# ruralhack-board-r2.net
KiCad netlist of a schematic drawn in EAGLE
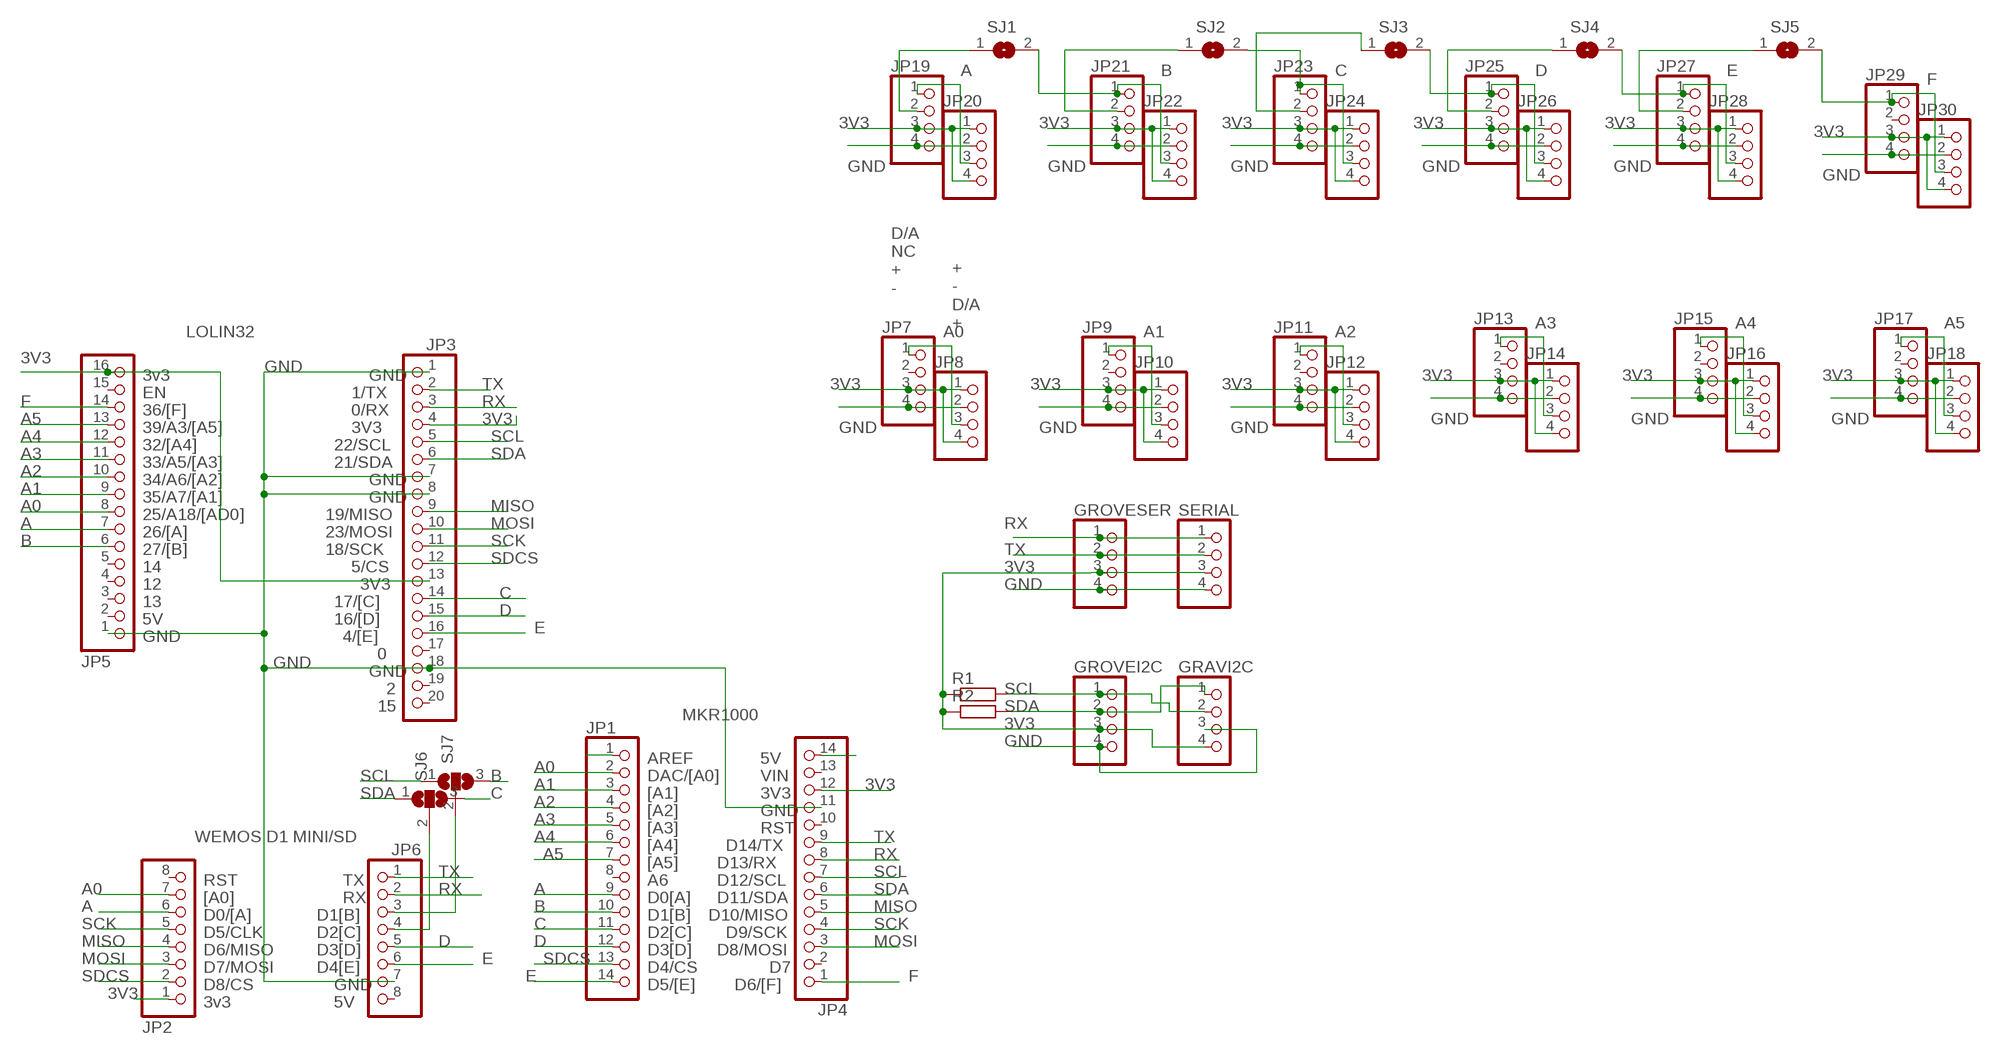
[diagram p0: schematic, sheet 1]

(export (version "E")
  (design (tool "Eeschema 10.0.6"))
  (components
    (comp (ref "GRAVI2C")
      (value "PINHD-1X4")
      (footprint "eagle-import:1X04")
      (libsource (lib "eagle-import") (part "PINHD-1X4"))
    )
    (comp (ref "GROVEI2C")
      (value "PINHD-1X4")
      (footprint "eagle-import:1X04")
      (libsource (lib "eagle-import") (part "PINHD-1X4"))
    )
    (comp (ref "GROVESER")
      (value "PINHD-1X4")
      (footprint "eagle-import:1X04")
      (libsource (lib "eagle-import") (part "PINHD-1X4"))
    )
    (comp (ref "JP1")
      (value "PINHD-1X14")
      (footprint "eagle-import:1X14")
      (libsource (lib "eagle-import") (part "PINHD-1X14"))
    )
    (comp (ref "JP2")
      (value "PINHD-1X8")
      (footprint "eagle-import:1X08")
      (libsource (lib "eagle-import") (part "PINHD-1X8"))
    )
    (comp (ref "JP3")
      (value "PINHD-1X20")
      (footprint "eagle-import:1X20")
      (libsource (lib "eagle-import") (part "PINHD-1X20"))
    )
    (comp (ref "JP4")
      (value "PINHD-1X14")
      (footprint "eagle-import:1X14")
      (libsource (lib "eagle-import") (part "PINHD-1X14"))
    )
    (comp (ref "JP5")
      (value "PINHD-1X16")
      (footprint "eagle-import:1X16")
      (libsource (lib "eagle-import") (part "PINHD-1X16"))
    )
    (comp (ref "JP6")
      (value "PINHD-1X8")
      (footprint "eagle-import:1X08")
      (libsource (lib "eagle-import") (part "PINHD-1X8"))
    )
    (comp (ref "JP7")
      (value "PINHD-1X4")
      (footprint "eagle-import:1X04")
      (libsource (lib "eagle-import") (part "PINHD-1X4"))
    )
    (comp (ref "JP8")
      (value "PINHD-1X4")
      (footprint "eagle-import:1X04")
      (libsource (lib "eagle-import") (part "PINHD-1X4"))
    )
    (comp (ref "JP9")
      (value "PINHD-1X4")
      (footprint "eagle-import:1X04")
      (libsource (lib "eagle-import") (part "PINHD-1X4"))
    )
    (comp (ref "JP10")
      (value "PINHD-1X4")
      (footprint "eagle-import:1X04")
      (libsource (lib "eagle-import") (part "PINHD-1X4"))
    )
    (comp (ref "JP11")
      (value "PINHD-1X4")
      (footprint "eagle-import:1X04")
      (libsource (lib "eagle-import") (part "PINHD-1X4"))
    )
    (comp (ref "JP12")
      (value "PINHD-1X4")
      (footprint "eagle-import:1X04")
      (libsource (lib "eagle-import") (part "PINHD-1X4"))
    )
    (comp (ref "JP13")
      (value "PINHD-1X4")
      (footprint "eagle-import:1X04")
      (libsource (lib "eagle-import") (part "PINHD-1X4"))
    )
    (comp (ref "JP14")
      (value "PINHD-1X4")
      (footprint "eagle-import:1X04")
      (libsource (lib "eagle-import") (part "PINHD-1X4"))
    )
    (comp (ref "JP15")
      (value "PINHD-1X4")
      (footprint "eagle-import:1X04")
      (libsource (lib "eagle-import") (part "PINHD-1X4"))
    )
    (comp (ref "JP16")
      (value "PINHD-1X4")
      (footprint "eagle-import:1X04")
      (libsource (lib "eagle-import") (part "PINHD-1X4"))
    )
    (comp (ref "JP17")
      (value "PINHD-1X4")
      (footprint "eagle-import:1X04")
      (libsource (lib "eagle-import") (part "PINHD-1X4"))
    )
    (comp (ref "JP18")
      (value "PINHD-1X4")
      (footprint "eagle-import:1X04")
      (libsource (lib "eagle-import") (part "PINHD-1X4"))
    )
    (comp (ref "JP19")
      (value "PINHD-1X4")
      (footprint "eagle-import:1X04")
      (libsource (lib "eagle-import") (part "PINHD-1X4"))
    )
    (comp (ref "JP20")
      (value "PINHD-1X4")
      (footprint "eagle-import:1X04")
      (libsource (lib "eagle-import") (part "PINHD-1X4"))
    )
    (comp (ref "JP21")
      (value "PINHD-1X4")
      (footprint "eagle-import:1X04")
      (libsource (lib "eagle-import") (part "PINHD-1X4"))
    )
    (comp (ref "JP22")
      (value "PINHD-1X4")
      (footprint "eagle-import:1X04")
      (libsource (lib "eagle-import") (part "PINHD-1X4"))
    )
    (comp (ref "JP23")
      (value "PINHD-1X4")
      (footprint "eagle-import:1X04")
      (libsource (lib "eagle-import") (part "PINHD-1X4"))
    )
    (comp (ref "JP24")
      (value "PINHD-1X4")
      (footprint "eagle-import:1X04")
      (libsource (lib "eagle-import") (part "PINHD-1X4"))
    )
    (comp (ref "JP25")
      (value "PINHD-1X4")
      (footprint "eagle-import:1X04")
      (libsource (lib "eagle-import") (part "PINHD-1X4"))
    )
    (comp (ref "JP26")
      (value "PINHD-1X4")
      (footprint "eagle-import:1X04")
      (libsource (lib "eagle-import") (part "PINHD-1X4"))
    )
    (comp (ref "JP27")
      (value "PINHD-1X4")
      (footprint "eagle-import:1X04")
      (libsource (lib "eagle-import") (part "PINHD-1X4"))
    )
    (comp (ref "JP28")
      (value "PINHD-1X4")
      (footprint "eagle-import:1X04")
      (libsource (lib "eagle-import") (part "PINHD-1X4"))
    )
    (comp (ref "JP29")
      (value "PINHD-1X4")
      (footprint "eagle-import:1X04")
      (libsource (lib "eagle-import") (part "PINHD-1X4"))
    )
    (comp (ref "JP30")
      (value "PINHD-1X4")
      (footprint "eagle-import:1X04")
      (libsource (lib "eagle-import") (part "PINHD-1X4"))
    )
    (comp (ref "R1")
      (value "R-EU_0204/7")
      (footprint "eagle-import:0204_7")
      (libsource (lib "eagle-import") (part "R-EU_0204/7"))
    )
    (comp (ref "R2")
      (value "R-EU_0204/7")
      (footprint "eagle-import:0204_7")
      (libsource (lib "eagle-import") (part "R-EU_0204/7"))
    )
    (comp (ref "SERIAL")
      (value "PINHD-1X4")
      (footprint "eagle-import:1X04")
      (libsource (lib "eagle-import") (part "PINHD-1X4"))
    )
    (comp (ref "SJ1")
      (value "SJW")
      (footprint "eagle-import:SJW")
      (libsource (lib "eagle-import") (part "SJW"))
    )
    (comp (ref "SJ2")
      (value "SJW")
      (footprint "eagle-import:SJW")
      (libsource (lib "eagle-import") (part "SJW"))
    )
    (comp (ref "SJ3")
      (value "SJW")
      (footprint "eagle-import:SJW")
      (libsource (lib "eagle-import") (part "SJW"))
    )
    (comp (ref "SJ4")
      (value "SJW")
      (footprint "eagle-import:SJW")
      (libsource (lib "eagle-import") (part "SJW"))
    )
    (comp (ref "SJ5")
      (value "SJW")
      (footprint "eagle-import:SJW")
      (libsource (lib "eagle-import") (part "SJW"))
    )
    (comp (ref "SJ6")
      (value "SJ2WW")
      (footprint "eagle-import:SJ_2W")
      (libsource (lib "eagle-import") (part "SJ2WW"))
    )
    (comp (ref "SJ7")
      (value "SJ2WW")
      (footprint "eagle-import:SJ_2W")
      (libsource (lib "eagle-import") (part "SJ2WW"))
    )
  )
  (nets
    (net (code "1") (name "/3V3") (class "Default")
      (node (ref "GRAVI2C") (pin "4") (pinfunction "4_4") (pintype "passive"))
      (node (ref "GROVEI2C") (pin "3") (pinfunction "3_3") (pintype "passive"))
      (node (ref "GROVESER") (pin "3") (pinfunction "3_3") (pintype "passive"))
      (node (ref "JP10") (pin "1") (pinfunction "1_1") (pintype "passive"))
      (node (ref "JP10") (pin "4") (pinfunction "4_4") (pintype "passive"))
      (node (ref "JP11") (pin "3") (pinfunction "3_3") (pintype "passive"))
      (node (ref "JP12") (pin "1") (pinfunction "1_1") (pintype "passive"))
      (node (ref "JP12") (pin "4") (pinfunction "4_4") (pintype "passive"))
      (node (ref "JP13") (pin "3") (pinfunction "3_3") (pintype "passive"))
      (node (ref "JP14") (pin "1") (pinfunction "1_1") (pintype "passive"))
      (node (ref "JP14") (pin "4") (pinfunction "4_4") (pintype "passive"))
      (node (ref "JP15") (pin "3") (pinfunction "3_3") (pintype "passive"))
      (node (ref "JP16") (pin "1") (pinfunction "1_1") (pintype "passive"))
      (node (ref "JP16") (pin "4") (pinfunction "4_4") (pintype "passive"))
      (node (ref "JP17") (pin "3") (pinfunction "3_3") (pintype "passive"))
      (node (ref "JP18") (pin "1") (pinfunction "1_1") (pintype "passive"))
      (node (ref "JP18") (pin "4") (pinfunction "4_4") (pintype "passive"))
      (node (ref "JP19") (pin "3") (pinfunction "3_3") (pintype "passive"))
      (node (ref "JP2") (pin "1") (pinfunction "1_1") (pintype "passive"))
      (node (ref "JP20") (pin "1") (pinfunction "1_1") (pintype "passive"))
      (node (ref "JP20") (pin "4") (pinfunction "4_4") (pintype "passive"))
      (node (ref "JP21") (pin "3") (pinfunction "3_3") (pintype "passive"))
      (node (ref "JP22") (pin "1") (pinfunction "1_1") (pintype "passive"))
      (node (ref "JP22") (pin "4") (pinfunction "4_4") (pintype "passive"))
      (node (ref "JP23") (pin "3") (pinfunction "3_3") (pintype "passive"))
      (node (ref "JP24") (pin "1") (pinfunction "1_1") (pintype "passive"))
      (node (ref "JP24") (pin "4") (pinfunction "4_4") (pintype "passive"))
      (node (ref "JP25") (pin "3") (pinfunction "3_3") (pintype "passive"))
      (node (ref "JP26") (pin "1") (pinfunction "1_1") (pintype "passive"))
      (node (ref "JP26") (pin "4") (pinfunction "4_4") (pintype "passive"))
      (node (ref "JP27") (pin "3") (pinfunction "3_3") (pintype "passive"))
      (node (ref "JP28") (pin "1") (pinfunction "1_1") (pintype "passive"))
      (node (ref "JP28") (pin "4") (pinfunction "4_4") (pintype "passive"))
      (node (ref "JP29") (pin "3") (pinfunction "3_3") (pintype "passive"))
      (node (ref "JP3") (pin "13") (pinfunction "13_13") (pintype "passive"))
      (node (ref "JP3") (pin "4") (pinfunction "4_4") (pintype "passive"))
      (node (ref "JP30") (pin "1") (pinfunction "1_1") (pintype "passive"))
      (node (ref "JP30") (pin "4") (pinfunction "4_4") (pintype "passive"))
      (node (ref "JP4") (pin "12") (pinfunction "12_12") (pintype "passive"))
      (node (ref "JP5") (pin "16") (pinfunction "16_16") (pintype "passive"))
      (node (ref "JP7") (pin "3") (pinfunction "3_3") (pintype "passive"))
      (node (ref "JP8") (pin "1") (pinfunction "1_1") (pintype "passive"))
      (node (ref "JP8") (pin "4") (pinfunction "4_4") (pintype "passive"))
      (node (ref "JP9") (pin "3") (pinfunction "3_3") (pintype "passive"))
      (node (ref "R1") (pin "1") (pinfunction "1_1") (pintype "passive"))
      (node (ref "R2") (pin "1") (pinfunction "1_1") (pintype "passive"))
      (node (ref "SERIAL") (pin "3") (pinfunction "3_3") (pintype "passive"))
    )
    (net (code "2") (name "/A") (class "Default")
      (node (ref "JP1") (pin "9") (pinfunction "9_9") (pintype "passive"))
      (node (ref "JP19") (pin "1") (pinfunction "1_1") (pintype "passive"))
      (node (ref "JP2") (pin "6") (pinfunction "6_6") (pintype "passive"))
      (node (ref "JP20") (pin "3") (pinfunction "3_3") (pintype "passive"))
      (node (ref "JP5") (pin "7") (pinfunction "7_7") (pintype "passive"))
    )
    (net (code "3") (name "/A0") (class "Default")
      (node (ref "JP1") (pin "2") (pinfunction "2_2") (pintype "passive"))
      (node (ref "JP2") (pin "7") (pinfunction "7_7") (pintype "passive"))
      (node (ref "JP5") (pin "8") (pinfunction "8_8") (pintype "passive"))
      (node (ref "JP7") (pin "1") (pinfunction "1_1") (pintype "passive"))
      (node (ref "JP8") (pin "3") (pinfunction "3_3") (pintype "passive"))
    )
    (net (code "4") (name "/A1") (class "Default")
      (node (ref "JP1") (pin "3") (pinfunction "3_3") (pintype "passive"))
      (node (ref "JP10") (pin "3") (pinfunction "3_3") (pintype "passive"))
      (node (ref "JP5") (pin "9") (pinfunction "9_9") (pintype "passive"))
      (node (ref "JP9") (pin "1") (pinfunction "1_1") (pintype "passive"))
    )
    (net (code "5") (name "/A2") (class "Default")
      (node (ref "JP1") (pin "4") (pinfunction "4_4") (pintype "passive"))
      (node (ref "JP11") (pin "1") (pinfunction "1_1") (pintype "passive"))
      (node (ref "JP12") (pin "3") (pinfunction "3_3") (pintype "passive"))
      (node (ref "JP5") (pin "10") (pinfunction "10_10") (pintype "passive"))
    )
    (net (code "6") (name "/A3") (class "Default")
      (node (ref "JP1") (pin "5") (pinfunction "5_5") (pintype "passive"))
      (node (ref "JP13") (pin "1") (pinfunction "1_1") (pintype "passive"))
      (node (ref "JP14") (pin "3") (pinfunction "3_3") (pintype "passive"))
      (node (ref "JP5") (pin "11") (pinfunction "11_11") (pintype "passive"))
    )
    (net (code "7") (name "/A4") (class "Default")
      (node (ref "JP1") (pin "6") (pinfunction "6_6") (pintype "passive"))
      (node (ref "JP15") (pin "1") (pinfunction "1_1") (pintype "passive"))
      (node (ref "JP16") (pin "3") (pinfunction "3_3") (pintype "passive"))
      (node (ref "JP5") (pin "12") (pinfunction "12_12") (pintype "passive"))
    )
    (net (code "8") (name "/A5") (class "Default")
      (node (ref "JP1") (pin "7") (pinfunction "7_7") (pintype "passive"))
      (node (ref "JP17") (pin "1") (pinfunction "1_1") (pintype "passive"))
      (node (ref "JP18") (pin "3") (pinfunction "3_3") (pintype "passive"))
      (node (ref "JP5") (pin "13") (pinfunction "13_13") (pintype "passive"))
    )
    (net (code "9") (name "/B") (class "Default")
      (node (ref "JP1") (pin "10") (pinfunction "10_10") (pintype "passive"))
      (node (ref "JP21") (pin "1") (pinfunction "1_1") (pintype "passive"))
      (node (ref "JP22") (pin "3") (pinfunction "3_3") (pintype "passive"))
      (node (ref "JP5") (pin "6") (pinfunction "6_6") (pintype "passive"))
      (node (ref "SJ1") (pin "2") (pinfunction "2_2") (pintype "passive"))
      (node (ref "SJ7") (pin "3") (pinfunction "3_3") (pintype "passive"))
    )
    (net (code "10") (name "/C") (class "Default")
      (node (ref "JP1") (pin "11") (pinfunction "11_11") (pintype "passive"))
      (node (ref "JP23") (pin "1") (pinfunction "1_1") (pintype "passive"))
      (node (ref "JP24") (pin "3") (pinfunction "3_3") (pintype "passive"))
      (node (ref "JP3") (pin "14") (pinfunction "14_14") (pintype "passive"))
      (node (ref "SJ2") (pin "2") (pinfunction "2_2") (pintype "passive"))
      (node (ref "SJ6") (pin "3") (pinfunction "3_3") (pintype "passive"))
    )
    (net (code "11") (name "/D") (class "Default")
      (node (ref "JP1") (pin "12") (pinfunction "12_12") (pintype "passive"))
      (node (ref "JP25") (pin "1") (pinfunction "1_1") (pintype "passive"))
      (node (ref "JP26") (pin "3") (pinfunction "3_3") (pintype "passive"))
      (node (ref "JP3") (pin "15") (pinfunction "15_15") (pintype "passive"))
      (node (ref "JP6") (pin "5") (pinfunction "5_5") (pintype "passive"))
      (node (ref "SJ3") (pin "2") (pinfunction "2_2") (pintype "passive"))
    )
    (net (code "12") (name "/E") (class "Default")
      (node (ref "JP1") (pin "14") (pinfunction "14_14") (pintype "passive"))
      (node (ref "JP27") (pin "1") (pinfunction "1_1") (pintype "passive"))
      (node (ref "JP28") (pin "3") (pinfunction "3_3") (pintype "passive"))
      (node (ref "JP3") (pin "16") (pinfunction "16_16") (pintype "passive"))
      (node (ref "JP6") (pin "6") (pinfunction "6_6") (pintype "passive"))
      (node (ref "SJ4") (pin "2") (pinfunction "2_2") (pintype "passive"))
    )
    (net (code "13") (name "/F") (class "Default")
      (node (ref "JP29") (pin "1") (pinfunction "1_1") (pintype "passive"))
      (node (ref "JP30") (pin "3") (pinfunction "3_3") (pintype "passive"))
      (node (ref "JP4") (pin "1") (pinfunction "1_1") (pintype "passive"))
      (node (ref "JP5") (pin "14") (pinfunction "14_14") (pintype "passive"))
      (node (ref "SJ5") (pin "2") (pinfunction "2_2") (pintype "passive"))
    )
    (net (code "14") (name "/GND") (class "Default")
      (node (ref "GRAVI2C") (pin "3") (pinfunction "3_3") (pintype "passive"))
      (node (ref "GROVEI2C") (pin "4") (pinfunction "4_4") (pintype "passive"))
      (node (ref "GROVESER") (pin "4") (pinfunction "4_4") (pintype "passive"))
      (node (ref "JP10") (pin "2") (pinfunction "2_2") (pintype "passive"))
      (node (ref "JP11") (pin "4") (pinfunction "4_4") (pintype "passive"))
      (node (ref "JP12") (pin "2") (pinfunction "2_2") (pintype "passive"))
      (node (ref "JP13") (pin "4") (pinfunction "4_4") (pintype "passive"))
      (node (ref "JP14") (pin "2") (pinfunction "2_2") (pintype "passive"))
      (node (ref "JP15") (pin "4") (pinfunction "4_4") (pintype "passive"))
      (node (ref "JP16") (pin "2") (pinfunction "2_2") (pintype "passive"))
      (node (ref "JP17") (pin "4") (pinfunction "4_4") (pintype "passive"))
      (node (ref "JP18") (pin "2") (pinfunction "2_2") (pintype "passive"))
      (node (ref "JP19") (pin "4") (pinfunction "4_4") (pintype "passive"))
      (node (ref "JP20") (pin "2") (pinfunction "2_2") (pintype "passive"))
      (node (ref "JP21") (pin "4") (pinfunction "4_4") (pintype "passive"))
      (node (ref "JP22") (pin "2") (pinfunction "2_2") (pintype "passive"))
      (node (ref "JP23") (pin "4") (pinfunction "4_4") (pintype "passive"))
      (node (ref "JP24") (pin "2") (pinfunction "2_2") (pintype "passive"))
      (node (ref "JP25") (pin "4") (pinfunction "4_4") (pintype "passive"))
      (node (ref "JP26") (pin "2") (pinfunction "2_2") (pintype "passive"))
      (node (ref "JP27") (pin "4") (pinfunction "4_4") (pintype "passive"))
      (node (ref "JP28") (pin "2") (pinfunction "2_2") (pintype "passive"))
      (node (ref "JP29") (pin "4") (pinfunction "4_4") (pintype "passive"))
      (node (ref "JP3") (pin "1") (pinfunction "1_1") (pintype "passive"))
      (node (ref "JP3") (pin "18") (pinfunction "18_18") (pintype "passive"))
      (node (ref "JP3") (pin "7") (pinfunction "7_7") (pintype "passive"))
      (node (ref "JP3") (pin "8") (pinfunction "8_8") (pintype "passive"))
      (node (ref "JP30") (pin "2") (pinfunction "2_2") (pintype "passive"))
      (node (ref "JP4") (pin "11") (pinfunction "11_11") (pintype "passive"))
      (node (ref "JP5") (pin "1") (pinfunction "1_1") (pintype "passive"))
      (node (ref "JP6") (pin "7") (pinfunction "7_7") (pintype "passive"))
      (node (ref "JP7") (pin "4") (pinfunction "4_4") (pintype "passive"))
      (node (ref "JP8") (pin "2") (pinfunction "2_2") (pintype "passive"))
      (node (ref "JP9") (pin "4") (pinfunction "4_4") (pintype "passive"))
      (node (ref "SERIAL") (pin "4") (pinfunction "4_4") (pintype "passive"))
    )
    (net (code "15") (name "/MISO") (class "Default")
      (node (ref "JP2") (pin "4") (pinfunction "4_4") (pintype "passive"))
      (node (ref "JP3") (pin "9") (pinfunction "9_9") (pintype "passive"))
      (node (ref "JP4") (pin "5") (pinfunction "5_5") (pintype "passive"))
    )
    (net (code "16") (name "/MOSI") (class "Default")
      (node (ref "JP2") (pin "3") (pinfunction "3_3") (pintype "passive"))
      (node (ref "JP3") (pin "10") (pinfunction "10_10") (pintype "passive"))
      (node (ref "JP4") (pin "3") (pinfunction "3_3") (pintype "passive"))
    )
    (net (code "17") (name "/RX") (class "Default")
      (node (ref "GROVESER") (pin "1") (pinfunction "1_1") (pintype "passive"))
      (node (ref "JP3") (pin "3") (pinfunction "3_3") (pintype "passive"))
      (node (ref "JP4") (pin "8") (pinfunction "8_8") (pintype "passive"))
      (node (ref "JP6") (pin "2") (pinfunction "2_2") (pintype "passive"))
      (node (ref "SERIAL") (pin "1") (pinfunction "1_1") (pintype "passive"))
    )
    (net (code "18") (name "/SCK") (class "Default")
      (node (ref "JP2") (pin "5") (pinfunction "5_5") (pintype "passive"))
      (node (ref "JP3") (pin "11") (pinfunction "11_11") (pintype "passive"))
      (node (ref "JP4") (pin "4") (pinfunction "4_4") (pintype "passive"))
    )
    (net (code "19") (name "/SCL") (class "Default")
      (node (ref "GRAVI2C") (pin "2") (pinfunction "2_2") (pintype "passive"))
      (node (ref "GROVEI2C") (pin "1") (pinfunction "1_1") (pintype "passive"))
      (node (ref "JP3") (pin "5") (pinfunction "5_5") (pintype "passive"))
      (node (ref "JP4") (pin "7") (pinfunction "7_7") (pintype "passive"))
      (node (ref "R1") (pin "2") (pinfunction "2_2") (pintype "passive"))
      (node (ref "SJ7") (pin "1") (pinfunction "1_1") (pintype "passive"))
    )
    (net (code "20") (name "/SDA") (class "Default")
      (node (ref "GRAVI2C") (pin "1") (pinfunction "1_1") (pintype "passive"))
      (node (ref "GROVEI2C") (pin "2") (pinfunction "2_2") (pintype "passive"))
      (node (ref "JP3") (pin "6") (pinfunction "6_6") (pintype "passive"))
      (node (ref "JP4") (pin "6") (pinfunction "6_6") (pintype "passive"))
      (node (ref "R2") (pin "2") (pinfunction "2_2") (pintype "passive"))
      (node (ref "SJ6") (pin "1") (pinfunction "1_1") (pintype "passive"))
    )
    (net (code "21") (name "/SDCS") (class "Default")
      (node (ref "JP1") (pin "13") (pinfunction "13_13") (pintype "passive"))
      (node (ref "JP2") (pin "2") (pinfunction "2_2") (pintype "passive"))
      (node (ref "JP3") (pin "12") (pinfunction "12_12") (pintype "passive"))
    )
    (net (code "22") (name "/TX") (class "Default")
      (node (ref "GROVESER") (pin "2") (pinfunction "2_2") (pintype "passive"))
      (node (ref "JP3") (pin "2") (pinfunction "2_2") (pintype "passive"))
      (node (ref "JP4") (pin "9") (pinfunction "9_9") (pintype "passive"))
      (node (ref "JP6") (pin "1") (pinfunction "1_1") (pintype "passive"))
      (node (ref "SERIAL") (pin "2") (pinfunction "2_2") (pintype "passive"))
    )
    (net (code "23") (name "Net-(JP6-Pad3)") (class "Default")
      (node (ref "JP6") (pin "3") (pinfunction "3_3") (pintype "passive"))
      (node (ref "SJ7") (pin "2") (pinfunction "2_2") (pintype "passive"))
    )
    (net (code "24") (name "Net-(JP6-Pad4)") (class "Default")
      (node (ref "JP6") (pin "4") (pinfunction "4_4") (pintype "passive"))
      (node (ref "SJ6") (pin "2") (pinfunction "2_2") (pintype "passive"))
    )
    (net (code "25") (name "Net-(JP19-Pad2)") (class "Default")
      (node (ref "JP19") (pin "2") (pinfunction "2_2") (pintype "passive"))
      (node (ref "SJ1") (pin "1") (pinfunction "1_1") (pintype "passive"))
    )
    (net (code "26") (name "Net-(JP21-Pad2)") (class "Default")
      (node (ref "JP21") (pin "2") (pinfunction "2_2") (pintype "passive"))
      (node (ref "SJ2") (pin "1") (pinfunction "1_1") (pintype "passive"))
    )
    (net (code "27") (name "Net-(JP23-Pad2)") (class "Default")
      (node (ref "JP23") (pin "2") (pinfunction "2_2") (pintype "passive"))
      (node (ref "SJ3") (pin "1") (pinfunction "1_1") (pintype "passive"))
    )
    (net (code "28") (name "Net-(JP25-Pad2)") (class "Default")
      (node (ref "JP25") (pin "2") (pinfunction "2_2") (pintype "passive"))
      (node (ref "SJ4") (pin "1") (pinfunction "1_1") (pintype "passive"))
    )
    (net (code "29") (name "Net-(JP27-Pad2)") (class "Default")
      (node (ref "JP27") (pin "2") (pinfunction "2_2") (pintype "passive"))
      (node (ref "SJ5") (pin "1") (pinfunction "1_1") (pintype "passive"))
    )
    (net (code "30") (name "unconnected-(JP1-Pad1)") (class "Default")
      (node (ref "JP1") (pin "1") (pinfunction "1_1") (pintype "passive"))
    )
    (net (code "31") (name "unconnected-(JP1-Pad8)") (class "Default")
      (node (ref "JP1") (pin "8") (pinfunction "8_8") (pintype "passive"))
    )
    (net (code "32") (name "unconnected-(JP2-Pad8)") (class "Default")
      (node (ref "JP2") (pin "8") (pinfunction "8_8") (pintype "passive"))
    )
    (net (code "33") (name "unconnected-(JP3-Pad17)") (class "Default")
      (node (ref "JP3") (pin "17") (pinfunction "17_17") (pintype "passive"))
    )
    (net (code "34") (name "unconnected-(JP3-Pad19)") (class "Default")
      (node (ref "JP3") (pin "19") (pinfunction "19_19") (pintype "passive"))
    )
    (net (code "35") (name "unconnected-(JP3-Pad20)") (class "Default")
      (node (ref "JP3") (pin "20") (pinfunction "20_20") (pintype "passive"))
    )
    (net (code "36") (name "unconnected-(JP4-Pad2)") (class "Default")
      (node (ref "JP4") (pin "2") (pinfunction "2_2") (pintype "passive"))
    )
    (net (code "37") (name "unconnected-(JP4-Pad10)") (class "Default")
      (node (ref "JP4") (pin "10") (pinfunction "10_10") (pintype "passive"))
    )
    (net (code "38") (name "unconnected-(JP4-Pad13)") (class "Default")
      (node (ref "JP4") (pin "13") (pinfunction "13_13") (pintype "passive"))
    )
    (net (code "39") (name "unconnected-(JP4-Pad14)") (class "Default")
      (node (ref "JP4") (pin "14") (pinfunction "14_14") (pintype "passive"))
    )
    (net (code "40") (name "unconnected-(JP5-Pad2)") (class "Default")
      (node (ref "JP5") (pin "2") (pinfunction "2_2") (pintype "passive"))
    )
    (net (code "41") (name "unconnected-(JP5-Pad3)") (class "Default")
      (node (ref "JP5") (pin "3") (pinfunction "3_3") (pintype "passive"))
    )
    (net (code "42") (name "unconnected-(JP5-Pad4)") (class "Default")
      (node (ref "JP5") (pin "4") (pinfunction "4_4") (pintype "passive"))
    )
    (net (code "43") (name "unconnected-(JP5-Pad5)") (class "Default")
      (node (ref "JP5") (pin "5") (pinfunction "5_5") (pintype "passive"))
    )
    (net (code "44") (name "unconnected-(JP5-Pad15)") (class "Default")
      (node (ref "JP5") (pin "15") (pinfunction "15_15") (pintype "passive"))
    )
    (net (code "45") (name "unconnected-(JP6-Pad8)") (class "Default")
      (node (ref "JP6") (pin "8") (pinfunction "8_8") (pintype "passive"))
    )
    (net (code "46") (name "unconnected-(JP7-Pad2)") (class "Default")
      (node (ref "JP7") (pin "2") (pinfunction "2_2") (pintype "passive"))
    )
    (net (code "47") (name "unconnected-(JP9-Pad2)") (class "Default")
      (node (ref "JP9") (pin "2") (pinfunction "2_2") (pintype "passive"))
    )
    (net (code "48") (name "unconnected-(JP11-Pad2)") (class "Default")
      (node (ref "JP11") (pin "2") (pinfunction "2_2") (pintype "passive"))
    )
    (net (code "49") (name "unconnected-(JP13-Pad2)") (class "Default")
      (node (ref "JP13") (pin "2") (pinfunction "2_2") (pintype "passive"))
    )
    (net (code "50") (name "unconnected-(JP15-Pad2)") (class "Default")
      (node (ref "JP15") (pin "2") (pinfunction "2_2") (pintype "passive"))
    )
    (net (code "51") (name "unconnected-(JP17-Pad2)") (class "Default")
      (node (ref "JP17") (pin "2") (pinfunction "2_2") (pintype "passive"))
    )
    (net (code "52") (name "unconnected-(JP29-Pad2)") (class "Default")
      (node (ref "JP29") (pin "2") (pinfunction "2_2") (pintype "passive"))
    )
  )
)
